# IMUinator2368.net
KiCad netlist of a schematic drawn in EAGLE
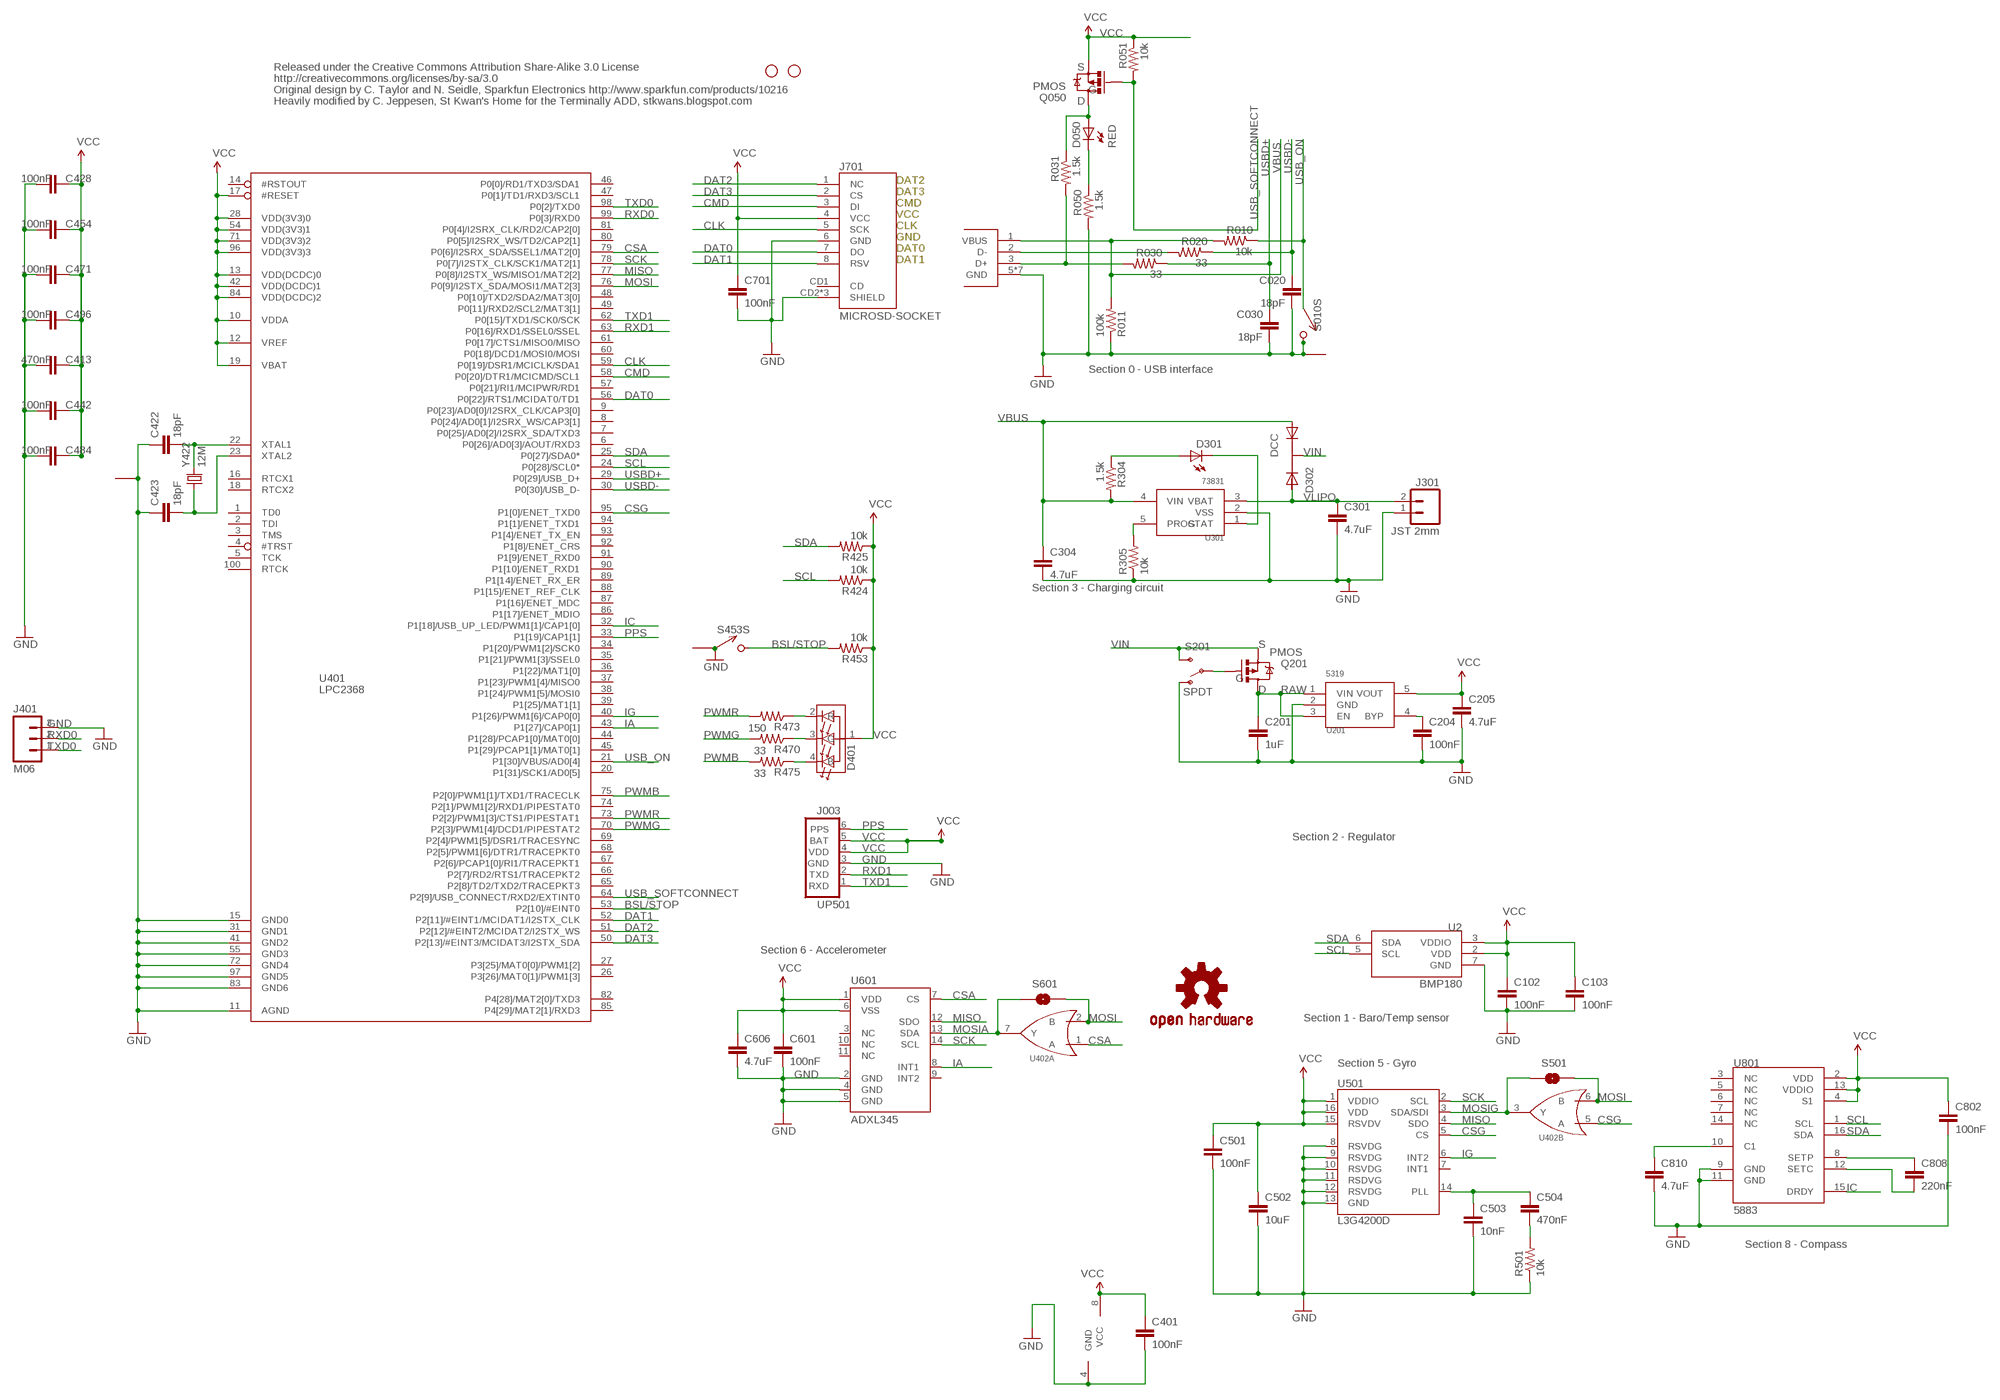
[diagram p0: schematic, sheet 1]

(export (version "E")
  (design (tool "Eeschema 10.0.6"))
  (components
    (comp (ref "C020")
      (value "18pF")
      (footprint "eagle-import:0402-CAP")
      (libsource (lib "eagle-import") (part "CAP0402-CAP"))
    )
    (comp (ref "C030")
      (value "18pF")
      (footprint "eagle-import:0402-CAP")
      (libsource (lib "eagle-import") (part "CAP0402-CAP"))
    )
    (comp (ref "C102")
      (value "100nF")
      (footprint "eagle-import:0402-CAP")
      (libsource (lib "eagle-import") (part "CAP0402-CAP"))
    )
    (comp (ref "C103")
      (value "100nF")
      (footprint "eagle-import:0402-CAP")
      (libsource (lib "eagle-import") (part "CAP0402-CAP"))
    )
    (comp (ref "C201")
      (value "1uF")
      (footprint "eagle-import:0402-CAP")
      (libsource (lib "eagle-import") (part "CAP0402-CAP"))
    )
    (comp (ref "C204")
      (value "100nF")
      (footprint "eagle-import:0402-CAP")
      (libsource (lib "eagle-import") (part "CAP0402-CAP"))
    )
    (comp (ref "C205")
      (value "4.7uF")
      (footprint "eagle-import:0402-CAP")
      (libsource (lib "eagle-import") (part "CAP0402-CAP"))
    )
    (comp (ref "C301")
      (value "4.7uF")
      (footprint "eagle-import:0402-CAP")
      (libsource (lib "eagle-import") (part "CAP0402-CAP"))
    )
    (comp (ref "C304")
      (value "4.7uF")
      (footprint "eagle-import:0402-CAP")
      (libsource (lib "eagle-import") (part "CAP0402-CAP"))
    )
    (comp (ref "C401")
      (value "100nF")
      (footprint "eagle-import:0402-CAP")
      (libsource (lib "eagle-import") (part "CAP0402-CAP"))
    )
    (comp (ref "C413")
      (value "470nF")
      (footprint "eagle-import:0402-CAP")
      (libsource (lib "eagle-import") (part "CAP0402-CAP"))
    )
    (comp (ref "C422")
      (value "18pF")
      (footprint "eagle-import:0402-CAP")
      (libsource (lib "eagle-import") (part "CAP0402-CAP"))
    )
    (comp (ref "C423")
      (value "18pF")
      (footprint "eagle-import:0402-CAP")
      (libsource (lib "eagle-import") (part "CAP0402-CAP"))
    )
    (comp (ref "C428")
      (value "100nF")
      (footprint "eagle-import:0402-CAP")
      (libsource (lib "eagle-import") (part "CAP0402-CAP"))
    )
    (comp (ref "C442")
      (value "100nF")
      (footprint "eagle-import:0402-CAP")
      (libsource (lib "eagle-import") (part "CAP0402-CAP"))
    )
    (comp (ref "C454")
      (value "100nF")
      (footprint "eagle-import:0402-CAP")
      (libsource (lib "eagle-import") (part "CAP0402-CAP"))
    )
    (comp (ref "C471")
      (value "100nF")
      (footprint "eagle-import:0402-CAP")
      (libsource (lib "eagle-import") (part "CAP0402-CAP"))
    )
    (comp (ref "C484")
      (value "100nF")
      (footprint "eagle-import:0402-CAP")
      (libsource (lib "eagle-import") (part "CAP0402-CAP"))
    )
    (comp (ref "C496")
      (value "100nF")
      (footprint "eagle-import:0402-CAP")
      (libsource (lib "eagle-import") (part "CAP0402-CAP"))
    )
    (comp (ref "C501")
      (value "100nF")
      (footprint "eagle-import:0402-CAP")
      (libsource (lib "eagle-import") (part "CAP0402-CAP"))
    )
    (comp (ref "C502")
      (value "10uF")
      (footprint "eagle-import:0603-CAP")
      (libsource (lib "eagle-import") (part "SparkFun-Passives_CAP0603-CAP"))
    )
    (comp (ref "C503")
      (value "10nF")
      (footprint "eagle-import:0402-CAP")
      (libsource (lib "eagle-import") (part "CAP0402-CAP"))
    )
    (comp (ref "C504")
      (value "470nF")
      (footprint "eagle-import:0402-CAP")
      (libsource (lib "eagle-import") (part "CAP0402-CAP"))
    )
    (comp (ref "C601")
      (value "100nF")
      (footprint "eagle-import:0402-CAP")
      (libsource (lib "eagle-import") (part "CAP0402-CAP"))
    )
    (comp (ref "C606")
      (value "4.7uF")
      (footprint "eagle-import:0402-CAP")
      (libsource (lib "eagle-import") (part "CAP0402-CAP"))
    )
    (comp (ref "C701")
      (value "100nF")
      (footprint "eagle-import:0402-CAP")
      (libsource (lib "eagle-import") (part "CAP0402-CAP"))
    )
    (comp (ref "C802")
      (value "100nF")
      (footprint "eagle-import:0402-CAP")
      (libsource (lib "eagle-import") (part "CAP0402-CAP"))
    )
    (comp (ref "C808")
      (value "220nF")
      (footprint "eagle-import:0402-CAP")
      (libsource (lib "eagle-import") (part "CAP0402-CAP"))
    )
    (comp (ref "C810")
      (value "4.7uF")
      (footprint "eagle-import:0402-CAP")
      (libsource (lib "eagle-import") (part "CAP0402-CAP"))
    )
    (comp (ref "D050")
      (value "RED")
      (footprint "eagle-import:LED-0603")
      (libsource (lib "eagle-import") (part "LED0603"))
    )
    (comp (ref "D301")
      (value "RED")
      (footprint "eagle-import:LED-0603")
      (libsource (lib "eagle-import") (part "LED0603"))
    )
    (comp (ref "D302")
      (value "DCC")
      (footprint "eagle-import:SOT-23-3")
      (libsource (lib "eagle-import") (part "PMEG2005CT"))
    )
    (comp (ref "D401")
      (value "RGB")
      (footprint "eagle-import:HSMF-C118")
      (libsource (lib "eagle-import") (part "HSMF-C118"))
    )
    (comp (ref "J001")
      (value "USB_MICROB_JST")
      (footprint "eagle-import:UB-MC5BR3-SD204-4S")
      (libsource (lib "eagle-import") (part "USB_MICROB_JST"))
    )
    (comp (ref "J003")
      (value "UP501")
      (footprint "eagle-import:UP501")
      (libsource (lib "eagle-import") (part "UP501"))
    )
    (comp (ref "J301")
      (value "JST 2mm")
      (footprint "eagle-import:JST-2-SMD")
      (libsource (lib "eagle-import") (part "M02-JST-2MM-SMT"))
    )
    (comp (ref "J401")
      (value "M06")
      (footprint "eagle-import:1X03")
      (libsource (lib "eagle-import") (part "M03PTH"))
    )
    (comp (ref "J701")
      (value "MICROSD-SOCKET")
      (footprint "eagle-import:MICROSD-SOCKET-PP")
      (libsource (lib "eagle-import") (part "MICROSD-SOCKET"))
    )
    (comp (ref "JP1")
      (value "STAND-OFF")
      (footprint "eagle-import:STAND-OFF")
      (libsource (lib "eagle-import") (part "STAND-OFF"))
    )
    (comp (ref "JP2")
      (value "STAND-OFF")
      (footprint "eagle-import:STAND-OFF")
      (libsource (lib "eagle-import") (part "STAND-OFF"))
    )
    (comp (ref "Q050")
      (value "PMOS")
      (footprint "eagle-import:SOT23-3")
      (libsource (lib "eagle-import") (part "MOSFET-PCHANNELSMD"))
    )
    (comp (ref "Q201")
      (value "PMOS")
      (footprint "eagle-import:SOT23-3")
      (libsource (lib "eagle-import") (part "MOSFET-PCHANNELSMD"))
    )
    (comp (ref "R010")
      (value "10k")
      (footprint "eagle-import:0402-RES")
      (libsource (lib "eagle-import") (part "RESISTOR0402-RES"))
    )
    (comp (ref "R011")
      (value "100k")
      (footprint "eagle-import:0402-RES")
      (libsource (lib "eagle-import") (part "RESISTOR0402-RES"))
    )
    (comp (ref "R020")
      (value "33")
      (footprint "eagle-import:0402-RES")
      (libsource (lib "eagle-import") (part "RESISTOR0402-RES"))
    )
    (comp (ref "R030")
      (value "33")
      (footprint "eagle-import:0402-RES")
      (libsource (lib "eagle-import") (part "RESISTOR0402-RES"))
    )
    (comp (ref "R031")
      (value "1.5k")
      (footprint "eagle-import:0402-RES")
      (libsource (lib "eagle-import") (part "RESISTOR0402-RES"))
    )
    (comp (ref "R050")
      (value "1.5k")
      (footprint "eagle-import:0402-RES")
      (libsource (lib "eagle-import") (part "RESISTOR0402-RES"))
    )
    (comp (ref "R051")
      (value "10k")
      (footprint "eagle-import:0402-RES")
      (libsource (lib "eagle-import") (part "RESISTOR0402-RES"))
    )
    (comp (ref "R304")
      (value "1.5k")
      (footprint "eagle-import:0402-RES")
      (libsource (lib "eagle-import") (part "RESISTOR0402-RES"))
    )
    (comp (ref "R305")
      (value "10k")
      (footprint "eagle-import:0402-RES")
      (libsource (lib "eagle-import") (part "RESISTOR0402-RES"))
    )
    (comp (ref "R424")
      (value "10k")
      (footprint "eagle-import:0402-RES")
      (libsource (lib "eagle-import") (part "SparkFun-Passives_RESISTOR0402-RES"))
    )
    (comp (ref "R425")
      (value "10k")
      (footprint "eagle-import:0402-RES")
      (libsource (lib "eagle-import") (part "SparkFun-Passives_RESISTOR0402-RES"))
    )
    (comp (ref "R453")
      (value "10k")
      (footprint "eagle-import:0402-RES")
      (libsource (lib "eagle-import") (part "SparkFun-Passives_RESISTOR0402-RES"))
    )
    (comp (ref "R470")
      (value "33")
      (footprint "eagle-import:0402-RES")
      (libsource (lib "eagle-import") (part "RESISTOR0402-RES"))
    )
    (comp (ref "R473")
      (value "150")
      (footprint "eagle-import:0402-RES")
      (libsource (lib "eagle-import") (part "RESISTOR0402-RES"))
    )
    (comp (ref "R475")
      (value "33")
      (footprint "eagle-import:0402-RES")
      (libsource (lib "eagle-import") (part "RESISTOR0402-RES"))
    )
    (comp (ref "R501")
      (value "10k")
      (footprint "eagle-import:0402-RES")
      (libsource (lib "eagle-import") (part "SparkFun-Passives_RESISTOR0402-RES"))
    )
    (comp (ref "S010")
      (value "SPST")
      (footprint "eagle-import:B3U-1100P")
      (fields (field (name "DIGIKEY") "SW1021CT-ND"))
      (libsource (lib "eagle-import") (part "B3U-1100P"))
    )
    (comp (ref "S201")
      (value "SPDT")
      (footprint "eagle-import:AYZ0202")
      (libsource (lib "eagle-import") (part "SWITCH-SPSTSMD"))
    )
    (comp (ref "S453")
      (value "SPST")
      (footprint "eagle-import:B3U-1100P")
      (fields (field (name "DIGIKEY") "SW1021CT-ND"))
      (libsource (lib "eagle-import") (part "B3U-1100P"))
    )
    (comp (ref "S501")
      (value "SOLDERJUMPERNO")
      (footprint "eagle-import:SJ_2S-NO")
      (libsource (lib "eagle-import") (part "SOLDERJUMPERNO"))
    )
    (comp (ref "S601")
      (value "SOLDERJUMPERNO")
      (footprint "eagle-import:SJ_2S-NO")
      (libsource (lib "eagle-import") (part "SOLDERJUMPERNO"))
    )
    (comp (ref "U$3")
      (value "OSHW-LOGOS")
      (footprint "eagle-import:OSHW-LOGO-S")
      (libsource (lib "eagle-import") (part "OSHW-LOGOS"))
    )
    (comp (ref "U2")
      (value "BMP180")
      (footprint "eagle-import:BMP180")
      (libsource (lib "eagle-import") (part "BMP180"))
    )
    (comp (ref "U201")
      (value "5319")
      (footprint "eagle-import:SOT-23-5")
      (libsource (lib "eagle-import") (part "MIC5319D5"))
    )
    (comp (ref "U301")
      (value "73831")
      (footprint "eagle-import:SOT-23-5")
      (libsource (lib "eagle-import") (part "MCP73831"))
    )
    (comp (ref "U401")
      (value "LPC2368")
      (footprint "eagle-import:LQFP100")
      (libsource (lib "eagle-import") (part "LPC2368"))
    )
    (comp (ref "U402")
      (value "7432")
      (footprint "eagle-import:DCU_8")
      (fields (field (name "DIGIKEY") "296-13268-1-ND"))
      (libsource (lib "eagle-import") (part "SN74LVC2G32"))
    )
    (comp (ref "U501")
      (value "L3G4200D")
      (footprint "eagle-import:LGA16-4X4")
      (libsource (lib "eagle-import") (part "L3G4200D"))
    )
    (comp (ref "U601")
      (value "ADXL345")
      (footprint "eagle-import:LGA14")
      (libsource (lib "eagle-import") (part "ADXL345"))
    )
    (comp (ref "U801")
      (value "5883")
      (footprint "eagle-import:16LPCC")
      (libsource (lib "eagle-import") (part "HMC5883LSMD"))
    )
    (comp (ref "Y422")
      (value "12M")
      (footprint "eagle-import:CRYSTAL_SMD")
      (fields (field (name "DIGIKEY") "887-1316-1-ND"))
      (libsource (lib "eagle-import") (part "TSX-3225"))
    )
  )
  (nets
    (net (code "1") (name "/BSL{slash}STOP") (class "Default")
      (node (ref "R453") (pin "2") (pinfunction "2_2") (pintype "passive"))
      (node (ref "S453") (pin "P$2") (pinfunction "2_P$2") (pintype "bidirectional"))
      (node (ref "U401") (pin "53") (pinfunction "P2[10]/#EINT0_53") (pintype "bidirectional"))
    )
    (net (code "2") (name "/CLK") (class "Default")
      (node (ref "J701") (pin "5") (pinfunction "SCK_5") (pintype "bidirectional"))
      (node (ref "U401") (pin "59") (pinfunction "P0[19]/DSR1/MCICLK/SDA1_59") (pintype "bidirectional"))
    )
    (net (code "3") (name "/CMD") (class "Default")
      (node (ref "J701") (pin "3") (pinfunction "DI_3") (pintype "bidirectional"))
      (node (ref "U401") (pin "58") (pinfunction "P0[20]/DTR1/MCICMD/SCL1_58") (pintype "bidirectional"))
    )
    (net (code "4") (name "/CSA") (class "Default")
      (node (ref "U401") (pin "79") (pinfunction "P0[6]/I2SRX_SDA/SSEL1/MAT2[0]_79") (pintype "bidirectional"))
      (node (ref "U402") (pin "1") (pinfunction "A_1") (pintype "bidirectional"))
      (node (ref "U601") (pin "7") (pinfunction "CS_7") (pintype "bidirectional"))
    )
    (net (code "5") (name "/CSG") (class "Default")
      (node (ref "U401") (pin "95") (pinfunction "P1[0]/ENET_TXD0_95") (pintype "bidirectional"))
      (node (ref "U402") (pin "5") (pinfunction "A_5") (pintype "bidirectional"))
      (node (ref "U501") (pin "5") (pinfunction "CS_5") (pintype "bidirectional"))
    )
    (net (code "6") (name "/DAT0") (class "Default")
      (node (ref "J701") (pin "7") (pinfunction "DO_7") (pintype "bidirectional"))
      (node (ref "U401") (pin "56") (pinfunction "P0[22]/RTS1/MCIDAT0/TD1_56") (pintype "bidirectional"))
    )
    (net (code "7") (name "/DAT1") (class "Default")
      (node (ref "J701") (pin "8") (pinfunction "RSV_8") (pintype "bidirectional"))
      (node (ref "U401") (pin "52") (pinfunction "P2[11]/#EINT1/MCIDAT1/I2STX_CLK_52") (pintype "bidirectional"))
    )
    (net (code "8") (name "/DAT2") (class "Default")
      (node (ref "J701") (pin "1") (pinfunction "NC_1") (pintype "bidirectional"))
      (node (ref "U401") (pin "51") (pinfunction "P2[12]/#EINT2/MCIDAT2/I2STX_WS_51") (pintype "bidirectional"))
    )
    (net (code "9") (name "/DAT3") (class "Default")
      (node (ref "J701") (pin "2") (pinfunction "CS_2") (pintype "bidirectional"))
      (node (ref "U401") (pin "50") (pinfunction "P2[13]/#EINT3/MCIDAT3/I2STX_SDA_50") (pintype "bidirectional"))
    )
    (net (code "10") (name "/IA") (class "Default")
      (node (ref "U401") (pin "43") (pinfunction "P1[27]/CAP0[1]_43") (pintype "bidirectional"))
      (node (ref "U601") (pin "8") (pinfunction "INT1_8") (pintype "bidirectional"))
    )
    (net (code "11") (name "/IC") (class "Default")
      (node (ref "U401") (pin "32") (pinfunction "P1[18]/USB_UP_LED/PWM1[1]/CAP1[0]_32") (pintype "bidirectional"))
      (node (ref "U801") (pin "15") (pinfunction "DRDY_15") (pintype "bidirectional"))
    )
    (net (code "12") (name "/IG") (class "Default")
      (node (ref "U401") (pin "40") (pinfunction "P1[26]/PWM1[6]/CAP0[0]_40") (pintype "bidirectional"))
      (node (ref "U501") (pin "6") (pinfunction "INT2_6") (pintype "bidirectional"))
    )
    (net (code "13") (name "/MISO") (class "Default")
      (node (ref "U401") (pin "77") (pinfunction "P0[8]/I2STX_WS/MISO1/MAT2[2]_77") (pintype "bidirectional"))
      (node (ref "U501") (pin "4") (pinfunction "SDO_4") (pintype "bidirectional"))
      (node (ref "U601") (pin "12") (pinfunction "SDO_12") (pintype "bidirectional"))
    )
    (net (code "14") (name "/MOSI") (class "Default")
      (node (ref "S501") (pin "2") (pinfunction "2_2") (pintype "passive"))
      (node (ref "S601") (pin "2") (pinfunction "2_2") (pintype "passive"))
      (node (ref "U401") (pin "76") (pinfunction "P0[9]/I2STX_SDA/MOSI1/MAT2[3]_76") (pintype "bidirectional"))
      (node (ref "U402") (pin "2") (pinfunction "B_2") (pintype "bidirectional"))
      (node (ref "U402") (pin "6") (pinfunction "B_6") (pintype "bidirectional"))
    )
    (net (code "15") (name "/MOSIA") (class "Default")
      (node (ref "S601") (pin "1") (pinfunction "1_1") (pintype "passive"))
      (node (ref "U402") (pin "7") (pinfunction "Y_7") (pintype "bidirectional"))
      (node (ref "U601") (pin "13") (pinfunction "SDA_13") (pintype "bidirectional"))
    )
    (net (code "16") (name "/MOSIG") (class "Default")
      (node (ref "S501") (pin "1") (pinfunction "1_1") (pintype "passive"))
      (node (ref "U402") (pin "3") (pinfunction "Y_3") (pintype "bidirectional"))
      (node (ref "U501") (pin "3") (pinfunction "SDA/SDI_3") (pintype "bidirectional"))
    )
    (net (code "17") (name "/PPS") (class "Default")
      (node (ref "J003") (pin "6") (pinfunction "PPS_6") (pintype "passive"))
      (node (ref "U401") (pin "33") (pinfunction "P1[19]/CAP1[1]_33") (pintype "bidirectional"))
    )
    (net (code "18") (name "/PWMB") (class "Default")
      (node (ref "R475") (pin "2") (pinfunction "2_2") (pintype "passive"))
      (node (ref "U401") (pin "75") (pinfunction "P2[0]/PWM1[1]/TXD1/TRACECLK_75") (pintype "bidirectional"))
    )
    (net (code "19") (name "/PWMG") (class "Default")
      (node (ref "R470") (pin "2") (pinfunction "2_2") (pintype "passive"))
      (node (ref "U401") (pin "70") (pinfunction "P2[3]/PWM1[4]/DCD1/PIPESTAT2_70") (pintype "bidirectional"))
    )
    (net (code "20") (name "/PWMR") (class "Default")
      (node (ref "R473") (pin "2") (pinfunction "2_2") (pintype "passive"))
      (node (ref "U401") (pin "73") (pinfunction "P2[2]/PWM1[3]/CTS1/PIPESTAT1_73") (pintype "bidirectional"))
    )
    (net (code "21") (name "/RAW") (class "Default")
      (node (ref "C201") (pin "1") (pinfunction "1_1") (pintype "passive"))
      (node (ref "Q201") (pin "3") (pinfunction "D_3") (pintype "passive"))
      (node (ref "U201") (pin "1") (pinfunction "VIN_1") (pintype "bidirectional"))
      (node (ref "U201") (pin "3") (pinfunction "EN_3") (pintype "bidirectional"))
    )
    (net (code "22") (name "/RXD0") (class "Default")
      (node (ref "J401") (pin "2") (pinfunction "2_2") (pintype "passive"))
      (node (ref "U401") (pin "99") (pinfunction "P0[3]/RXD0_99") (pintype "bidirectional"))
    )
    (net (code "23") (name "/RXD1") (class "Default")
      (node (ref "J003") (pin "2") (pinfunction "TXD_2") (pintype "passive"))
      (node (ref "U401") (pin "63") (pinfunction "P0[16]/RXD1/SSEL0/SSEL_63") (pintype "bidirectional"))
    )
    (net (code "24") (name "/SCK") (class "Default")
      (node (ref "U401") (pin "78") (pinfunction "P0[7]/I2STX_CLK/SCK1/MAT2[1]_78") (pintype "bidirectional"))
      (node (ref "U501") (pin "2") (pinfunction "SCL_2") (pintype "bidirectional"))
      (node (ref "U601") (pin "14") (pinfunction "SCL_14") (pintype "bidirectional"))
    )
    (net (code "25") (name "/SCL") (class "Default")
      (node (ref "R424") (pin "2") (pinfunction "2_2") (pintype "passive"))
      (node (ref "U2") (pin "5") (pinfunction "SCL_5") (pintype "input"))
      (node (ref "U401") (pin "24") (pinfunction "P0[28]/SCL0*_24") (pintype "bidirectional"))
      (node (ref "U801") (pin "1") (pinfunction "SCL_1") (pintype "bidirectional"))
    )
    (net (code "26") (name "/SDA") (class "Default")
      (node (ref "R425") (pin "2") (pinfunction "2_2") (pintype "passive"))
      (node (ref "U2") (pin "6") (pinfunction "SDA_6") (pintype "bidirectional"))
      (node (ref "U401") (pin "25") (pinfunction "P0[27]/SDA0*_25") (pintype "bidirectional"))
      (node (ref "U801") (pin "16") (pinfunction "SDA_16") (pintype "bidirectional"))
    )
    (net (code "27") (name "/TXD0") (class "Default")
      (node (ref "J401") (pin "1") (pinfunction "1_1") (pintype "passive"))
      (node (ref "U401") (pin "98") (pinfunction "P0[2]/TXD0_98") (pintype "bidirectional"))
    )
    (net (code "28") (name "/TXD1") (class "Default")
      (node (ref "J003") (pin "1") (pinfunction "RXD_1") (pintype "passive"))
      (node (ref "U401") (pin "62") (pinfunction "P0[15]/TXD1/SCK0/SCK_62") (pintype "bidirectional"))
    )
    (net (code "29") (name "/USBD+") (class "Default")
      (node (ref "C030") (pin "1") (pinfunction "1_1") (pintype "passive"))
      (node (ref "R030") (pin "1") (pinfunction "1_1") (pintype "passive"))
      (node (ref "U401") (pin "29") (pinfunction "P0[29]/USB_D+_29") (pintype "bidirectional"))
    )
    (net (code "30") (name "/USBD-") (class "Default")
      (node (ref "C020") (pin "1") (pinfunction "1_1") (pintype "passive"))
      (node (ref "R020") (pin "1") (pinfunction "1_1") (pintype "passive"))
      (node (ref "U401") (pin "30") (pinfunction "P0[30]/USB_D-_30") (pintype "bidirectional"))
    )
    (net (code "31") (name "/USB_ON") (class "Default")
      (node (ref "R010") (pin "1") (pinfunction "1_1") (pintype "passive"))
      (node (ref "S010") (pin "P$1") (pinfunction "1_P$1") (pintype "bidirectional"))
      (node (ref "U401") (pin "21") (pinfunction "P1[30]/VBUS/AD0[4]_21") (pintype "bidirectional"))
    )
    (net (code "32") (name "/USB_SOFTCONNECT") (class "Default")
      (node (ref "Q050") (pin "1") (pinfunction "G_1") (pintype "passive"))
      (node (ref "R051") (pin "2") (pinfunction "2_2") (pintype "passive"))
      (node (ref "U401") (pin "64") (pinfunction "P2[9]/USB_CONNECT/RXD2/EXTINT0_64") (pintype "bidirectional"))
    )
    (net (code "33") (name "/VBUS") (class "Default")
      (node (ref "C304") (pin "1") (pinfunction "1_1") (pintype "passive"))
      (node (ref "D302") (pin "1") (pinfunction "A1_1") (pintype "passive"))
      (node (ref "J001") (pin "1") (pinfunction "VBUS_1") (pintype "bidirectional"))
      (node (ref "R010") (pin "2") (pinfunction "2_2") (pintype "passive"))
      (node (ref "R011") (pin "2") (pinfunction "2_2") (pintype "passive"))
      (node (ref "R304") (pin "2") (pinfunction "2_2") (pintype "passive"))
      (node (ref "U301") (pin "4") (pinfunction "VIN_4") (pintype "bidirectional"))
    )
    (net (code "34") (name "/VIN") (class "Default")
      (node (ref "D302") (pin "3") (pinfunction "K_3") (pintype "passive"))
      (node (ref "Q201") (pin "2") (pinfunction "S_2") (pintype "passive"))
      (node (ref "S201") (pin "3") (pinfunction "S_3") (pintype "passive"))
    )
    (net (code "35") (name "/VLIPO") (class "Default")
      (node (ref "C301") (pin "1") (pinfunction "1_1") (pintype "passive"))
      (node (ref "D302") (pin "2") (pinfunction "A2_2") (pintype "passive"))
      (node (ref "J301") (pin "2") (pinfunction "2_2") (pintype "passive"))
      (node (ref "U301") (pin "3") (pinfunction "VBAT_3") (pintype "bidirectional"))
    )
    (net (code "36") (name "GND") (class "Default")
      (node (ref "C020") (pin "2") (pinfunction "2_2") (pintype "passive"))
      (node (ref "C030") (pin "2") (pinfunction "2_2") (pintype "passive"))
      (node (ref "C102") (pin "2") (pinfunction "2_2") (pintype "passive"))
      (node (ref "C103") (pin "2") (pinfunction "2_2") (pintype "passive"))
      (node (ref "C201") (pin "2") (pinfunction "2_2") (pintype "passive"))
      (node (ref "C204") (pin "2") (pinfunction "2_2") (pintype "passive"))
      (node (ref "C205") (pin "2") (pinfunction "2_2") (pintype "passive"))
      (node (ref "C301") (pin "2") (pinfunction "2_2") (pintype "passive"))
      (node (ref "C304") (pin "2") (pinfunction "2_2") (pintype "passive"))
      (node (ref "C401") (pin "2") (pinfunction "2_2") (pintype "passive"))
      (node (ref "C413") (pin "2") (pinfunction "2_2") (pintype "passive"))
      (node (ref "C422") (pin "1") (pinfunction "1_1") (pintype "passive"))
      (node (ref "C423") (pin "1") (pinfunction "1_1") (pintype "passive"))
      (node (ref "C428") (pin "2") (pinfunction "2_2") (pintype "passive"))
      (node (ref "C442") (pin "2") (pinfunction "2_2") (pintype "passive"))
      (node (ref "C454") (pin "2") (pinfunction "2_2") (pintype "passive"))
      (node (ref "C471") (pin "2") (pinfunction "2_2") (pintype "passive"))
      (node (ref "C484") (pin "2") (pinfunction "2_2") (pintype "passive"))
      (node (ref "C496") (pin "2") (pinfunction "2_2") (pintype "passive"))
      (node (ref "C501") (pin "2") (pinfunction "2_2") (pintype "passive"))
      (node (ref "C502") (pin "2") (pinfunction "2_2") (pintype "passive"))
      (node (ref "C503") (pin "2") (pinfunction "2_2") (pintype "passive"))
      (node (ref "C601") (pin "2") (pinfunction "2_2") (pintype "passive"))
      (node (ref "C606") (pin "2") (pinfunction "2_2") (pintype "passive"))
      (node (ref "C701") (pin "2") (pinfunction "2_2") (pintype "passive"))
      (node (ref "C802") (pin "2") (pinfunction "2_2") (pintype "passive"))
      (node (ref "C810") (pin "2") (pinfunction "2_2") (pintype "passive"))
      (node (ref "J001") (pin "5") (pinfunction "GND_5") (pintype "bidirectional"))
      (node (ref "J001") (pin "P$10") (pinfunction "GND_P$10") (pintype "bidirectional"))
      (node (ref "J001") (pin "P$11") (pinfunction "GND_P$11") (pintype "bidirectional"))
      (node (ref "J001") (pin "P$6") (pinfunction "GND_P$6") (pintype "bidirectional"))
      (node (ref "J001") (pin "P$7") (pinfunction "GND_P$7") (pintype "bidirectional"))
      (node (ref "J001") (pin "P$8") (pinfunction "GND_P$8") (pintype "bidirectional"))
      (node (ref "J001") (pin "P$9") (pinfunction "GND_P$9") (pintype "bidirectional"))
      (node (ref "J003") (pin "3") (pinfunction "GND_3") (pintype "passive"))
      (node (ref "J301") (pin "1") (pinfunction "1_1") (pintype "passive"))
      (node (ref "J401") (pin "3") (pinfunction "3_3") (pintype "passive"))
      (node (ref "J701") (pin "6") (pinfunction "GND_6") (pintype "bidirectional"))
      (node (ref "J701") (pin "CD2") (pinfunction "SHIELD_CD2") (pintype "bidirectional"))
      (node (ref "J701") (pin "GND1") (pinfunction "SHIELD_GND1") (pintype "bidirectional"))
      (node (ref "J701") (pin "GND3") (pinfunction "SHIELD_GND3") (pintype "bidirectional"))
      (node (ref "R011") (pin "1") (pinfunction "1_1") (pintype "passive"))
      (node (ref "R050") (pin "2") (pinfunction "2_2") (pintype "passive"))
      (node (ref "R305") (pin "1") (pinfunction "1_1") (pintype "passive"))
      (node (ref "R501") (pin "1") (pinfunction "1_1") (pintype "passive"))
      (node (ref "S010") (pin "P$2") (pinfunction "2_P$2") (pintype "bidirectional"))
      (node (ref "S010") (pin "P$3") (pinfunction "1_P$3") (pintype "bidirectional"))
      (node (ref "S201") (pin "1") (pinfunction "O_1") (pintype "passive"))
      (node (ref "S453") (pin "P$1") (pinfunction "1_P$1") (pintype "bidirectional"))
      (node (ref "S453") (pin "P$3") (pinfunction "1_P$3") (pintype "bidirectional"))
      (node (ref "U2") (pin "7") (pinfunction "GND_7") (pintype "power_in"))
      (node (ref "U201") (pin "2") (pinfunction "GND_2") (pintype "bidirectional"))
      (node (ref "U301") (pin "2") (pinfunction "VSS_2") (pintype "bidirectional"))
      (node (ref "U401") (pin "11") (pinfunction "AGND_11") (pintype "bidirectional"))
      (node (ref "U401") (pin "15") (pinfunction "GND0_15") (pintype "bidirectional"))
      (node (ref "U401") (pin "31") (pinfunction "GND1_31") (pintype "bidirectional"))
      (node (ref "U401") (pin "41") (pinfunction "GND2_41") (pintype "bidirectional"))
      (node (ref "U401") (pin "55") (pinfunction "GND3_55") (pintype "bidirectional"))
      (node (ref "U401") (pin "72") (pinfunction "GND4_72") (pintype "bidirectional"))
      (node (ref "U401") (pin "83") (pinfunction "GND6_83") (pintype "bidirectional"))
      (node (ref "U401") (pin "97") (pinfunction "GND5_97") (pintype "bidirectional"))
      (node (ref "U402") (pin "4") (pinfunction "GND_4") (pintype "bidirectional"))
      (node (ref "U501") (pin "10") (pinfunction "RSVDG_10") (pintype "bidirectional"))
      (node (ref "U501") (pin "11") (pinfunction "RSDVG_11") (pintype "bidirectional"))
      (node (ref "U501") (pin "12") (pinfunction "RSVDG_12") (pintype "bidirectional"))
      (node (ref "U501") (pin "13") (pinfunction "GND_13") (pintype "bidirectional"))
      (node (ref "U501") (pin "8") (pinfunction "RSVDG_8") (pintype "bidirectional"))
      (node (ref "U501") (pin "9") (pinfunction "RSVDG_9") (pintype "bidirectional"))
      (node (ref "U601") (pin "2") (pinfunction "GND_2") (pintype "bidirectional"))
      (node (ref "U601") (pin "4") (pinfunction "GND_4") (pintype "bidirectional"))
      (node (ref "U601") (pin "5") (pinfunction "GND_5") (pintype "bidirectional"))
      (node (ref "U801") (pin "11") (pinfunction "GND_11") (pintype "bidirectional"))
      (node (ref "U801") (pin "9") (pinfunction "GND_9") (pintype "bidirectional"))
      (node (ref "Y422") (pin "2") (pinfunction "1_2") (pintype "bidirectional"))
      (node (ref "Y422") (pin "4") (pinfunction "1_4") (pintype "bidirectional"))
    )
    (net (code "37") (name "Net-(C504-Pad2)") (class "Default")
      (node (ref "C504") (pin "2") (pinfunction "2_2") (pintype "passive"))
      (node (ref "R501") (pin "2") (pinfunction "2_2") (pintype "passive"))
    )
    (net (code "38") (name "Net-(D050-PadC)") (class "Default")
      (node (ref "D050") (pin "C") (pinfunction "C_C") (pintype "passive"))
      (node (ref "R050") (pin "1") (pinfunction "1_1") (pintype "passive"))
    )
    (net (code "39") (name "Net-(D301-PadA)") (class "Default")
      (node (ref "D301") (pin "A") (pinfunction "A_A") (pintype "passive"))
      (node (ref "R304") (pin "1") (pinfunction "1_1") (pintype "passive"))
    )
    (net (code "40") (name "Net-(D401-B)") (class "Default")
      (node (ref "D401") (pin "4") (pinfunction "B_4") (pintype "passive"))
      (node (ref "R475") (pin "1") (pinfunction "1_1") (pintype "passive"))
    )
    (net (code "41") (name "Net-(D401-G)") (class "Default")
      (node (ref "D401") (pin "3") (pinfunction "G_3") (pintype "passive"))
      (node (ref "R470") (pin "1") (pinfunction "1_1") (pintype "passive"))
    )
    (net (code "42") (name "Net-(D401-R)") (class "Default")
      (node (ref "D401") (pin "2") (pinfunction "R_2") (pintype "passive"))
      (node (ref "R473") (pin "1") (pinfunction "1_1") (pintype "passive"))
    )
    (net (code "43") (name "Net-(J001-D+)") (class "Default")
      (node (ref "J001") (pin "3") (pinfunction "D+_3") (pintype "bidirectional"))
      (node (ref "R030") (pin "2") (pinfunction "2_2") (pintype "passive"))
      (node (ref "R031") (pin "2") (pinfunction "2_2") (pintype "passive"))
    )
    (net (code "44") (name "Net-(J001-D-)") (class "Default")
      (node (ref "J001") (pin "2") (pinfunction "D-_2") (pintype "bidirectional"))
      (node (ref "R020") (pin "2") (pinfunction "2_2") (pintype "passive"))
    )
    (net (code "45") (name "Net-(Q050-D)") (class "Default")
      (node (ref "D050") (pin "A") (pinfunction "A_A") (pintype "passive"))
      (node (ref "Q050") (pin "3") (pinfunction "D_3") (pintype "passive"))
      (node (ref "R031") (pin "1") (pinfunction "1_1") (pintype "passive"))
    )
    (net (code "46") (name "Net-(Q201-G)") (class "Default")
      (node (ref "Q201") (pin "1") (pinfunction "G_1") (pintype "passive"))
      (node (ref "S201") (pin "2") (pinfunction "P_2") (pintype "passive"))
    )
    (net (code "47") (name "Net-(U201-BYP)") (class "Default")
      (node (ref "C204") (pin "1") (pinfunction "1_1") (pintype "passive"))
      (node (ref "U201") (pin "4") (pinfunction "BYP_4") (pintype "bidirectional"))
    )
    (net (code "48") (name "Net-(U301-PROG)") (class "Default")
      (node (ref "R305") (pin "2") (pinfunction "2_2") (pintype "passive"))
      (node (ref "U301") (pin "5") (pinfunction "PROG_5") (pintype "bidirectional"))
    )
    (net (code "49") (name "Net-(U301-STAT)") (class "Default")
      (node (ref "D301") (pin "C") (pinfunction "C_C") (pintype "passive"))
      (node (ref "U301") (pin "1") (pinfunction "STAT_1") (pintype "bidirectional"))
    )
    (net (code "50") (name "Net-(U401-XTAL1)") (class "Default")
      (node (ref "C422") (pin "2") (pinfunction "2_2") (pintype "passive"))
      (node (ref "U401") (pin "22") (pinfunction "XTAL1_22") (pintype "bidirectional"))
      (node (ref "Y422") (pin "3") (pinfunction "2_3") (pintype "passive"))
    )
    (net (code "51") (name "Net-(U401-XTAL2)") (class "Default")
      (node (ref "C423") (pin "2") (pinfunction "2_2") (pintype "passive"))
      (node (ref "U401") (pin "23") (pinfunction "XTAL2_23") (pintype "bidirectional"))
      (node (ref "Y422") (pin "1") (pinfunction "1_1") (pintype "passive"))
    )
    (net (code "52") (name "Net-(U501-PLL)") (class "Default")
      (node (ref "C503") (pin "1") (pinfunction "1_1") (pintype "passive"))
      (node (ref "C504") (pin "1") (pinfunction "1_1") (pintype "passive"))
      (node (ref "U501") (pin "14") (pinfunction "PLL_14") (pintype "bidirectional"))
    )
    (net (code "53") (name "Net-(U801-C1)") (class "Default")
      (node (ref "C810") (pin "1") (pinfunction "1_1") (pintype "passive"))
      (node (ref "U801") (pin "10") (pinfunction "C1_10") (pintype "bidirectional"))
    )
    (net (code "54") (name "Net-(U801-SETC)") (class "Default")
      (node (ref "C808") (pin "2") (pinfunction "2_2") (pintype "passive"))
      (node (ref "U801") (pin "12") (pinfunction "SETC_12") (pintype "bidirectional"))
    )
    (net (code "55") (name "Net-(U801-SETP)") (class "Default")
      (node (ref "C808") (pin "1") (pinfunction "1_1") (pintype "passive"))
      (node (ref "U801") (pin "8") (pinfunction "SETP_8") (pintype "bidirectional"))
    )
    (net (code "56") (name "VCC") (class "Default")
      (node (ref "C102") (pin "1") (pinfunction "1_1") (pintype "passive"))
      (node (ref "C103") (pin "1") (pinfunction "1_1") (pintype "passive"))
      (node (ref "C205") (pin "1") (pinfunction "1_1") (pintype "passive"))
      (node (ref "C401") (pin "1") (pinfunction "1_1") (pintype "passive"))
      (node (ref "C413") (pin "1") (pinfunction "1_1") (pintype "passive"))
      (node (ref "C428") (pin "1") (pinfunction "1_1") (pintype "passive"))
      (node (ref "C442") (pin "1") (pinfunction "1_1") (pintype "passive"))
      (node (ref "C454") (pin "1") (pinfunction "1_1") (pintype "passive"))
      (node (ref "C471") (pin "1") (pinfunction "1_1") (pintype "passive"))
      (node (ref "C484") (pin "1") (pinfunction "1_1") (pintype "passive"))
      (node (ref "C496") (pin "1") (pinfunction "1_1") (pintype "passive"))
      (node (ref "C501") (pin "1") (pinfunction "1_1") (pintype "passive"))
      (node (ref "C502") (pin "1") (pinfunction "1_1") (pintype "passive"))
      (node (ref "C601") (pin "1") (pinfunction "1_1") (pintype "passive"))
      (node (ref "C606") (pin "1") (pinfunction "1_1") (pintype "passive"))
      (node (ref "C701") (pin "1") (pinfunction "1_1") (pintype "passive"))
      (node (ref "C802") (pin "1") (pinfunction "1_1") (pintype "passive"))
      (node (ref "D401") (pin "1") (pinfunction "A_1") (pintype "passive"))
      (node (ref "J003") (pin "4") (pinfunction "VDD_4") (pintype "passive"))
      (node (ref "J003") (pin "5") (pinfunction "BAT_5") (pintype "passive"))
      (node (ref "J701") (pin "4") (pinfunction "VCC_4") (pintype "bidirectional"))
      (node (ref "Q050") (pin "2") (pinfunction "S_2") (pintype "passive"))
      (node (ref "R051") (pin "1") (pinfunction "1_1") (pintype "passive"))
      (node (ref "R424") (pin "1") (pinfunction "1_1") (pintype "passive"))
      (node (ref "R425") (pin "1") (pinfunction "1_1") (pintype "passive"))
      (node (ref "R453") (pin "1") (pinfunction "1_1") (pintype "passive"))
      (node (ref "U2") (pin "2") (pinfunction "VDD_2") (pintype "power_in"))
      (node (ref "U2") (pin "3") (pinfunction "VDDIO_3") (pintype "power_in"))
      (node (ref "U201") (pin "5") (pinfunction "VOUT_5") (pintype "bidirectional"))
      (node (ref "U401") (pin "10") (pinfunction "VDDA_10") (pintype "bidirectional"))
      (node (ref "U401") (pin "12") (pinfunction "VREF_12") (pintype "bidirectional"))
      (node (ref "U401") (pin "13") (pinfunction "VDD(DCDC)0_13") (pintype "bidirectional"))
      (node (ref "U401") (pin "17") (pinfunction "#RESET_17") (pintype "bidirectional"))
      (node (ref "U401") (pin "19") (pinfunction "VBAT_19") (pintype "bidirectional"))
      (node (ref "U401") (pin "28") (pinfunction "VDD(3V3)0_28") (pintype "bidirectional"))
      (node (ref "U401") (pin "42") (pinfunction "VDD(DCDC)1_42") (pintype "bidirectional"))
      (node (ref "U401") (pin "54") (pinfunction "VDD(3V3)1_54") (pintype "bidirectional"))
      (node (ref "U401") (pin "71") (pinfunction "VDD(3V3)2_71") (pintype "bidirectional"))
      (node (ref "U401") (pin "84") (pinfunction "VDD(DCDC)2_84") (pintype "bidirectional"))
      (node (ref "U401") (pin "96") (pinfunction "VDD(3V3)3_96") (pintype "bidirectional"))
      (node (ref "U402") (pin "8") (pinfunction "VCC_8") (pintype "bidirectional"))
      (node (ref "U501") (pin "1") (pinfunction "VDDIO_1") (pintype "bidirectional"))
      (node (ref "U501") (pin "15") (pinfunction "RSVDV_15") (pintype "bidirectional"))
      (node (ref "U501") (pin "16") (pinfunction "VDD_16") (pintype "bidirectional"))
      (node (ref "U601") (pin "1") (pinfunction "VDD_1") (pintype "bidirectional"))
      (node (ref "U601") (pin "6") (pinfunction "VSS_6") (pintype "bidirectional"))
      (node (ref "U801") (pin "13") (pinfunction "VDDIO_13") (pintype "bidirectional"))
      (node (ref "U801") (pin "2") (pinfunction "VDD_2") (pintype "bidirectional"))
      (node (ref "U801") (pin "4") (pinfunction "S1_4") (pintype "bidirectional"))
    )
    (net (code "57") (name "unconnected-(J701-CD-PadCD1)") (class "Default")
      (node (ref "J701") (pin "CD1") (pinfunction "CD_CD1") (pintype "bidirectional"))
    )
    (net (code "58") (name "unconnected-(U401-#RSTOUT-Pad14)") (class "Default")
      (node (ref "U401") (pin "14") (pinfunction "#RSTOUT_14") (pintype "bidirectional"))
    )
    (net (code "59") (name "unconnected-(U401-#TRST-Pad4)") (class "Default")
      (node (ref "U401") (pin "4") (pinfunction "#TRST_4") (pintype "bidirectional"))
    )
    (net (code "60") (name "unconnected-(U401-P0[0]{slash}RD1{slash}TXD3{slash}SDA1-Pad46)") (class "Default")
      (node (ref "U401") (pin "46") (pinfunction "P0[0]/RD1/TXD3/SDA1_46") (pintype "bidirectional"))
    )
    (net (code "61") (name "unconnected-(U401-P0[1]{slash}TD1{slash}RXD3{slash}SCL1-Pad47)") (class "Default")
      (node (ref "U401") (pin "47") (pinfunction "P0[1]/TD1/RXD3/SCL1_47") (pintype "bidirectional"))
    )
    (net (code "62") (name "unconnected-(U401-P0[4]{slash}I2SRX_CLK{slash}RD2{slash}CAP2[0]-Pad81)") (class "Default")
      (node (ref "U401") (pin "81") (pinfunction "P0[4]/I2SRX_CLK/RD2/CAP2[0]_81") (pintype "bidirectional"))
    )
    (net (code "63") (name "unconnected-(U401-P0[5]{slash}I2SRX_WS{slash}TD2{slash}CAP2[1]-Pad80)") (class "Default")
      (node (ref "U401") (pin "80") (pinfunction "P0[5]/I2SRX_WS/TD2/CAP2[1]_80") (pintype "bidirectional"))
    )
    (net (code "64") (name "unconnected-(U401-P0[10]{slash}TXD2{slash}SDA2{slash}MAT3[0]-Pad48)") (class "Default")
      (node (ref "U401") (pin "48") (pinfunction "P0[10]/TXD2/SDA2/MAT3[0]_48") (pintype "bidirectional"))
    )
    (net (code "65") (name "unconnected-(U401-P0[11]{slash}RXD2{slash}SCL2{slash}MAT3[1]-Pad49)") (class "Default")
      (node (ref "U401") (pin "49") (pinfunction "P0[11]/RXD2/SCL2/MAT3[1]_49") (pintype "bidirectional"))
    )
    (net (code "66") (name "unconnected-(U401-P0[17]{slash}CTS1{slash}MISO0{slash}MISO-Pad61)") (class "Default")
      (node (ref "U401") (pin "61") (pinfunction "P0[17]/CTS1/MISO0/MISO_61") (pintype "bidirectional"))
    )
    (net (code "67") (name "unconnected-(U401-P0[18]{slash}DCD1{slash}MOSI0{slash}MOSI-Pad60)") (class "Default")
      (node (ref "U401") (pin "60") (pinfunction "P0[18]/DCD1/MOSI0/MOSI_60") (pintype "bidirectional"))
    )
    (net (code "68") (name "unconnected-(U401-P0[21]{slash}RI1{slash}MCIPWR{slash}RD1-Pad57)") (class "Default")
      (node (ref "U401") (pin "57") (pinfunction "P0[21]/RI1/MCIPWR/RD1_57") (pintype "bidirectional"))
    )
    (net (code "69") (name "unconnected-(U401-P0[23]{slash}AD0[0]{slash}I2SRX_CLK{slash}CAP3[0]-Pad9)") (class "Default")
      (node (ref "U401") (pin "9") (pinfunction "P0[23]/AD0[0]/I2SRX_CLK/CAP3[0]_9") (pintype "bidirectional"))
    )
    (net (code "70") (name "unconnected-(U401-P0[24]{slash}AD0[1]{slash}I2SRX_WS{slash}CAP3[1]-Pad8)") (class "Default")
      (node (ref "U401") (pin "8") (pinfunction "P0[24]/AD0[1]/I2SRX_WS/CAP3[1]_8") (pintype "bidirectional"))
    )
    (net (code "71") (name "unconnected-(U401-P0[25]{slash}AD0[2]{slash}I2SRX_SDA{slash}TXD3-Pad7)") (class "Default")
      (node (ref "U401") (pin "7") (pinfunction "P0[25]/AD0[2]/I2SRX_SDA/TXD3_7") (pintype "bidirectional"))
    )
    (net (code "72") (name "unconnected-(U401-P0[26]{slash}AD0[3]{slash}AOUT{slash}RXD3-Pad6)") (class "Default")
      (node (ref "U401") (pin "6") (pinfunction "P0[26]/AD0[3]/AOUT/RXD3_6") (pintype "bidirectional"))
    )
    (net (code "73") (name "unconnected-(U401-P1[1]{slash}ENET_TXD1-Pad94)") (class "Default")
      (node (ref "U401") (pin "94") (pinfunction "P1[1]/ENET_TXD1_94") (pintype "bidirectional"))
    )
    (net (code "74") (name "unconnected-(U401-P1[4]{slash}ENET_TX_EN-Pad93)") (class "Default")
      (node (ref "U401") (pin "93") (pinfunction "P1[4]/ENET_TX_EN_93") (pintype "bidirectional"))
    )
    (net (code "75") (name "unconnected-(U401-P1[8]{slash}ENET_CRS-Pad92)") (class "Default")
      (node (ref "U401") (pin "92") (pinfunction "P1[8]/ENET_CRS_92") (pintype "bidirectional"))
    )
    (net (code "76") (name "unconnected-(U401-P1[9]{slash}ENET_RXD0-Pad91)") (class "Default")
      (node (ref "U401") (pin "91") (pinfunction "P1[9]/ENET_RXD0_91") (pintype "bidirectional"))
    )
    (net (code "77") (name "unconnected-(U401-P1[10]{slash}ENET_RXD1-Pad90)") (class "Default")
      (node (ref "U401") (pin "90") (pinfunction "P1[10]/ENET_RXD1_90") (pintype "bidirectional"))
    )
    (net (code "78") (name "unconnected-(U401-P1[14]{slash}ENET_RX_ER-Pad89)") (class "Default")
      (node (ref "U401") (pin "89") (pinfunction "P1[14]/ENET_RX_ER_89") (pintype "bidirectional"))
    )
    (net (code "79") (name "unconnected-(U401-P1[15]{slash}ENET_REF_CLK-Pad88)") (class "Default")
      (node (ref "U401") (pin "88") (pinfunction "P1[15]/ENET_REF_CLK_88") (pintype "bidirectional"))
    )
    (net (code "80") (name "unconnected-(U401-P1[16]{slash}ENET_MDC-Pad87)") (class "Default")
      (node (ref "U401") (pin "87") (pinfunction "P1[16]/ENET_MDC_87") (pintype "bidirectional"))
    )
    (net (code "81") (name "unconnected-(U401-P1[17]{slash}ENET_MDIO-Pad86)") (class "Default")
      (node (ref "U401") (pin "86") (pinfunction "P1[17]/ENET_MDIO_86") (pintype "bidirectional"))
    )
    (net (code "82") (name "unconnected-(U401-P1[20]{slash}PWM1[2]{slash}SCK0-Pad34)") (class "Default")
      (node (ref "U401") (pin "34") (pinfunction "P1[20]/PWM1[2]/SCK0_34") (pintype "bidirectional"))
    )
    (net (code "83") (name "unconnected-(U401-P1[21]{slash}PWM1[3]{slash}SSEL0-Pad35)") (class "Default")
      (node (ref "U401") (pin "35") (pinfunction "P1[21]/PWM1[3]/SSEL0_35") (pintype "bidirectional"))
    )
    (net (code "84") (name "unconnected-(U401-P1[22]{slash}MAT1[0]-Pad36)") (class "Default")
      (node (ref "U401") (pin "36") (pinfunction "P1[22]/MAT1[0]_36") (pintype "bidirectional"))
    )
    (net (code "85") (name "unconnected-(U401-P1[23]{slash}PWM1[4]{slash}MISO0-Pad37)") (class "Default")
      (node (ref "U401") (pin "37") (pinfunction "P1[23]/PWM1[4]/MISO0_37") (pintype "bidirectional"))
    )
    (net (code "86") (name "unconnected-(U401-P1[24]{slash}PWM1[5]{slash}MOSI0-Pad38)") (class "Default")
      (node (ref "U401") (pin "38") (pinfunction "P1[24]/PWM1[5]/MOSI0_38") (pintype "bidirectional"))
    )
    (net (code "87") (name "unconnected-(U401-P1[25]{slash}MAT1[1]-Pad39)") (class "Default")
      (node (ref "U401") (pin "39") (pinfunction "P1[25]/MAT1[1]_39") (pintype "bidirectional"))
    )
    (net (code "88") (name "unconnected-(U401-P1[28]{slash}PCAP1[0]{slash}MAT0[0]-Pad44)") (class "Default")
      (node (ref "U401") (pin "44") (pinfunction "P1[28]/PCAP1[0]/MAT0[0]_44") (pintype "bidirectional"))
    )
    (net (code "89") (name "unconnected-(U401-P1[29]{slash}PCAP1[1]{slash}MAT0[1]-Pad45)") (class "Default")
      (node (ref "U401") (pin "45") (pinfunction "P1[29]/PCAP1[1]/MAT0[1]_45") (pintype "bidirectional"))
    )
    (net (code "90") (name "unconnected-(U401-P1[31]{slash}SCK1{slash}AD0[5]-Pad20)") (class "Default")
      (node (ref "U401") (pin "20") (pinfunction "P1[31]/SCK1/AD0[5]_20") (pintype "bidirectional"))
    )
    (net (code "91") (name "unconnected-(U401-P2[1]{slash}PWM1[2]{slash}RXD1{slash}PIPESTAT0-Pad74)") (class "Default")
      (node (ref "U401") (pin "74") (pinfunction "P2[1]/PWM1[2]/RXD1/PIPESTAT0_74") (pintype "bidirectional"))
    )
    (net (code "92") (name "unconnected-(U401-P2[4]{slash}PWM1[5]{slash}DSR1{slash}TRACESYNC-Pad69)") (class "Default")
      (node (ref "U401") (pin "69") (pinfunction "P2[4]/PWM1[5]/DSR1/TRACESYNC_69") (pintype "bidirectional"))
    )
    (net (code "93") (name "unconnected-(U401-P2[5]{slash}PWM1[6]{slash}DTR1{slash}TRACEPKT0-Pad68)") (class "Default")
      (node (ref "U401") (pin "68") (pinfunction "P2[5]/PWM1[6]/DTR1/TRACEPKT0_68") (pintype "bidirectional"))
    )
    (net (code "94") (name "unconnected-(U401-P2[6]{slash}PCAP1[0]{slash}RI1{slash}TRACEPKT1-Pad67)") (class "Default")
      (node (ref "U401") (pin "67") (pinfunction "P2[6]/PCAP1[0]/RI1/TRACEPKT1_67") (pintype "bidirectional"))
    )
    (net (code "95") (name "unconnected-(U401-P2[7]{slash}RD2{slash}RTS1{slash}TRACEPKT2-Pad66)") (class "Default")
      (node (ref "U401") (pin "66") (pinfunction "P2[7]/RD2/RTS1/TRACEPKT2_66") (pintype "bidirectional"))
    )
    (net (code "96") (name "unconnected-(U401-P2[8]{slash}TD2{slash}TXD2{slash}TRACEPKT3-Pad65)") (class "Default")
      (node (ref "U401") (pin "65") (pinfunction "P2[8]/TD2/TXD2/TRACEPKT3_65") (pintype "bidirectional"))
    )
    (net (code "97") (name "unconnected-(U401-P3[25]{slash}MAT0[0]{slash}PWM1[2]-Pad27)") (class "Default")
      (node (ref "U401") (pin "27") (pinfunction "P3[25]/MAT0[0]/PWM1[2]_27") (pintype "bidirectional"))
    )
    (net (code "98") (name "unconnected-(U401-P3[26]{slash}MAT0[1]{slash}PWM1[3]-Pad26)") (class "Default")
      (node (ref "U401") (pin "26") (pinfunction "P3[26]/MAT0[1]/PWM1[3]_26") (pintype "bidirectional"))
    )
    (net (code "99") (name "unconnected-(U401-P4[28]{slash}MAT2[0]{slash}TXD3-Pad82)") (class "Default")
      (node (ref "U401") (pin "82") (pinfunction "P4[28]/MAT2[0]/TXD3_82") (pintype "bidirectional"))
    )
    (net (code "100") (name "unconnected-(U401-P4[29]{slash}MAT2[1]{slash}RXD3-Pad85)") (class "Default")
      (node (ref "U401") (pin "85") (pinfunction "P4[29]/MAT2[1]/RXD3_85") (pintype "bidirectional"))
    )
    (net (code "101") (name "unconnected-(U401-RTCK-Pad100)") (class "Default")
      (node (ref "U401") (pin "100") (pinfunction "RTCK_100") (pintype "bidirectional"))
    )
    (net (code "102") (name "unconnected-(U401-RTCX1-Pad16)") (class "Default")
      (node (ref "U401") (pin "16") (pinfunction "RTCX1_16") (pintype "bidirectional"))
    )
    (net (code "103") (name "unconnected-(U401-RTCX2-Pad18)") (class "Default")
      (node (ref "U401") (pin "18") (pinfunction "RTCX2_18") (pintype "bidirectional"))
    )
    (net (code "104") (name "unconnected-(U401-TCK-Pad5)") (class "Default")
      (node (ref "U401") (pin "5") (pinfunction "TCK_5") (pintype "bidirectional"))
    )
    (net (code "105") (name "unconnected-(U401-TD0-Pad1)") (class "Default")
      (node (ref "U401") (pin "1") (pinfunction "TD0_1") (pintype "bidirectional"))
    )
    (net (code "106") (name "unconnected-(U401-TDI-Pad2)") (class "Default")
      (node (ref "U401") (pin "2") (pinfunction "TDI_2") (pintype "bidirectional"))
    )
    (net (code "107") (name "unconnected-(U401-TMS-Pad3)") (class "Default")
      (node (ref "U401") (pin "3") (pinfunction "TMS_3") (pintype "bidirectional"))
    )
    (net (code "108") (name "unconnected-(U501-INT1-Pad7)") (class "Default")
      (node (ref "U501") (pin "7") (pinfunction "INT1_7") (pintype "bidirectional"))
    )
    (net (code "109") (name "unconnected-(U601-INT2-Pad9)") (class "Default")
      (node (ref "U601") (pin "9") (pinfunction "INT2_9") (pintype "bidirectional"))
    )
    (net (code "110") (name "unconnected-(U601-NC-Pad3)") (class "Default")
      (node (ref "U601") (pin "3") (pinfunction "NC_3") (pintype "bidirectional"))
    )
    (net (code "111") (name "unconnected-(U601-NC-Pad10)") (class "Default")
      (node (ref "U601") (pin "10") (pinfunction "NC_10") (pintype "bidirectional"))
    )
    (net (code "112") (name "unconnected-(U601-NC-Pad11)") (class "Default")
      (node (ref "U601") (pin "11") (pinfunction "NC_11") (pintype "bidirectional"))
    )
    (net (code "113") (name "unconnected-(U801-NC-Pad3)") (class "Default")
      (node (ref "U801") (pin "3") (pinfunction "NC_3") (pintype "bidirectional"))
    )
    (net (code "114") (name "unconnected-(U801-NC-Pad5)") (class "Default")
      (node (ref "U801") (pin "5") (pinfunction "NC_5") (pintype "bidirectional"))
    )
    (net (code "115") (name "unconnected-(U801-NC-Pad6)") (class "Default")
      (node (ref "U801") (pin "6") (pinfunction "NC_6") (pintype "bidirectional"))
    )
    (net (code "116") (name "unconnected-(U801-NC-Pad7)") (class "Default")
      (node (ref "U801") (pin "7") (pinfunction "NC_7") (pintype "bidirectional"))
    )
    (net (code "117") (name "unconnected-(U801-NC-Pad14)") (class "Default")
      (node (ref "U801") (pin "14") (pinfunction "NC_14") (pintype "bidirectional"))
    )
  )
)
